# mcu_side.net
KiCad netlist of a schematic drawn in EAGLE
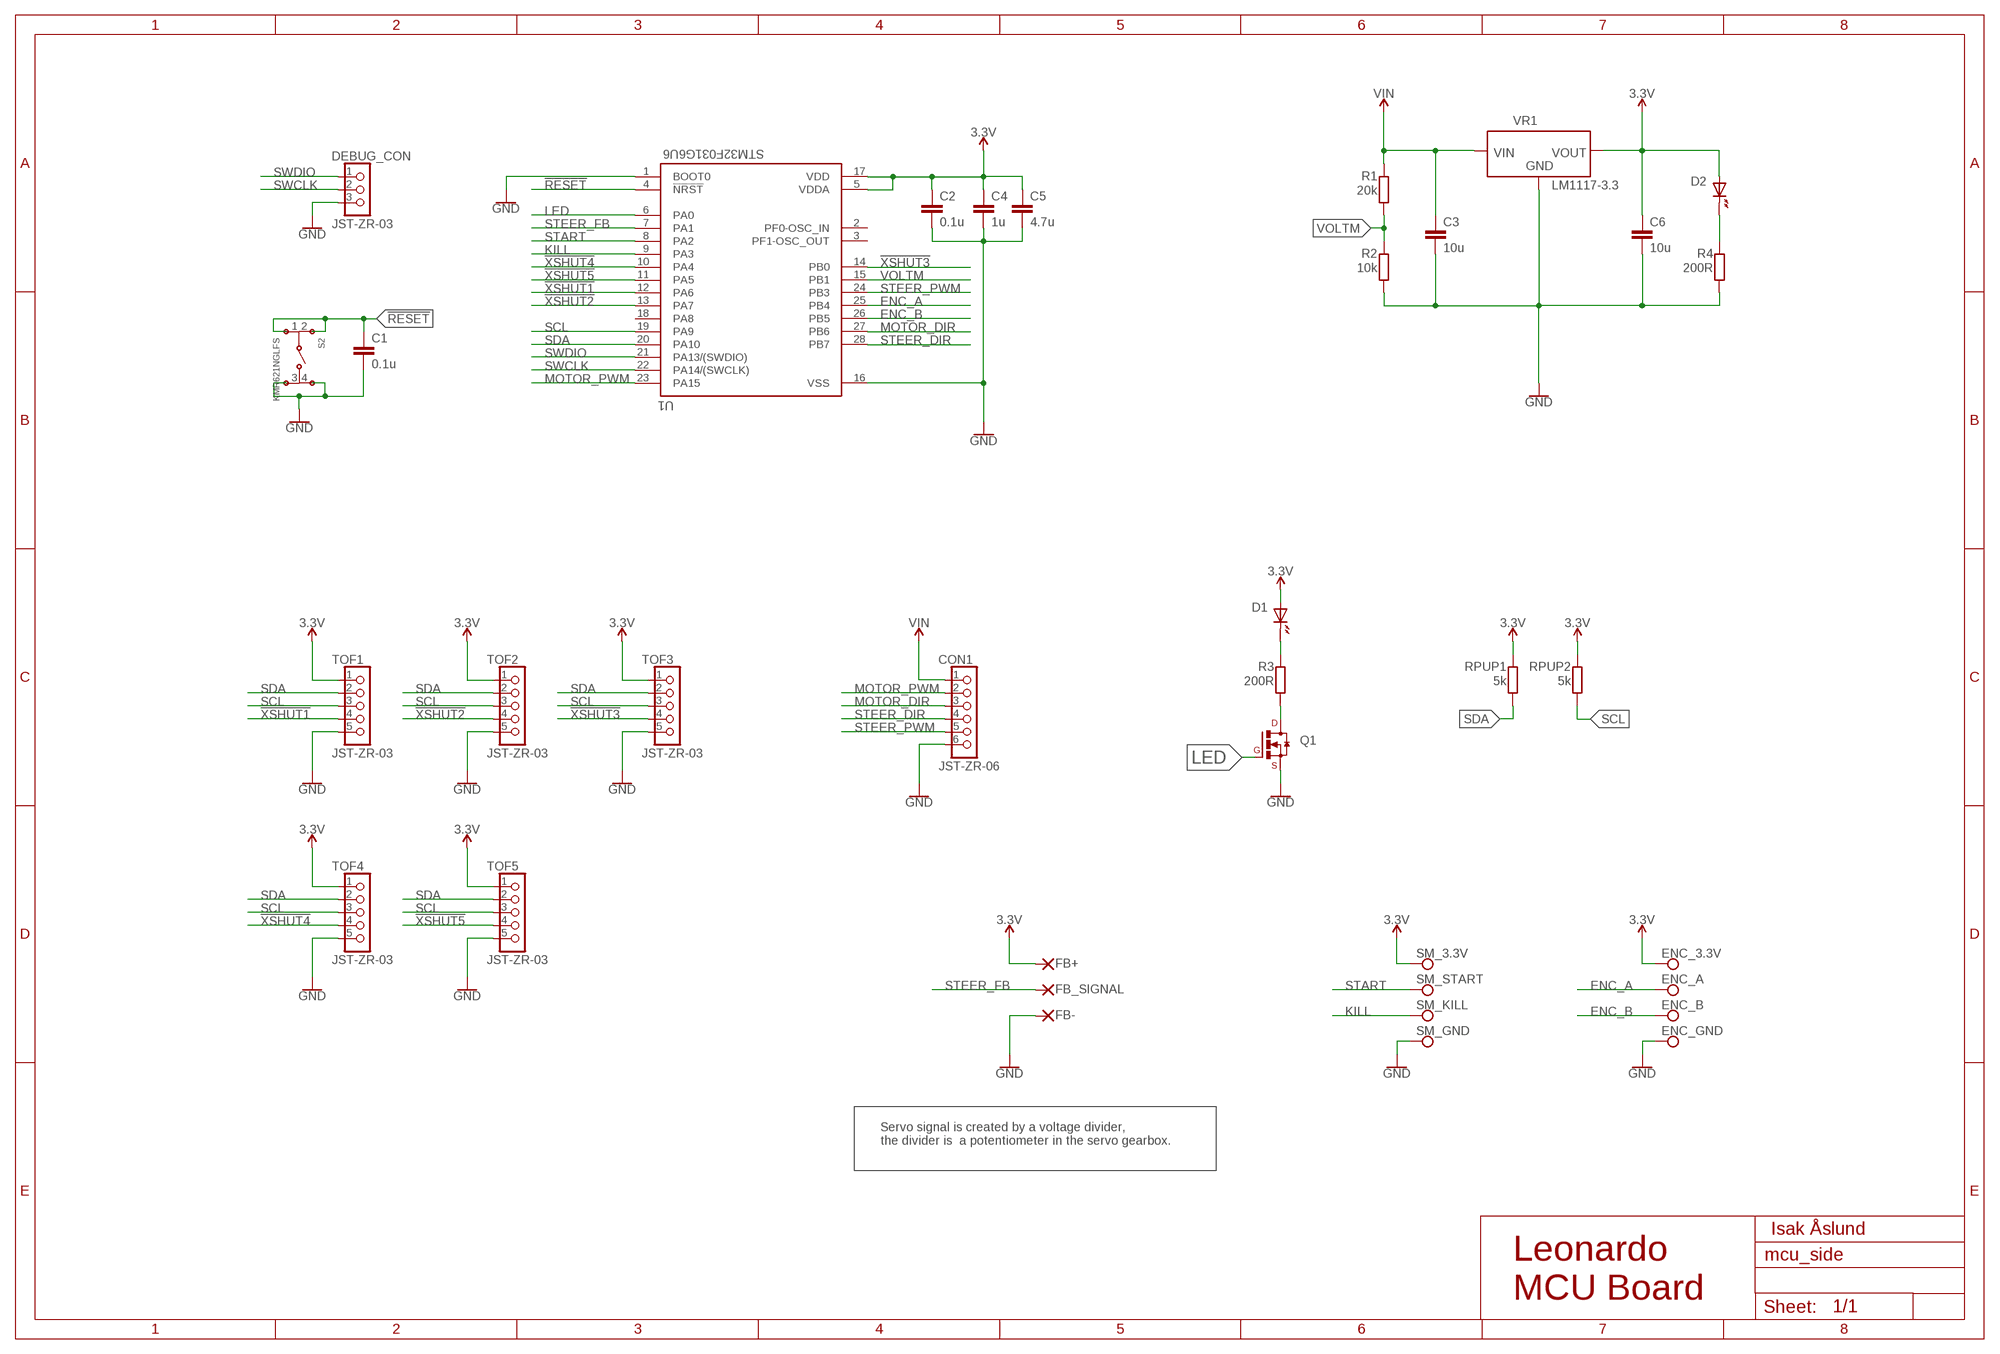
[diagram p0: schematic, sheet 1]

(export (version "E")
  (design (tool "Eeschema 10.0.6"))
  (components
    (comp (ref "C1")
      (value "0.1u")
      (footprint "eagle-import:C0603")
      (libsource (lib "eagle-import") (part "C0603"))
    )
    (comp (ref "C2")
      (value "0.1u")
      (footprint "eagle-import:C0603")
      (libsource (lib "eagle-import") (part "C0603"))
    )
    (comp (ref "C3")
      (value "10u")
      (footprint "eagle-import:C1206")
      (libsource (lib "eagle-import") (part "C1206"))
    )
    (comp (ref "C4")
      (value "1u")
      (footprint "eagle-import:C0603")
      (libsource (lib "eagle-import") (part "C0603"))
    )
    (comp (ref "C5")
      (value "4.7u")
      (footprint "eagle-import:C0603")
      (libsource (lib "eagle-import") (part "C0603"))
    )
    (comp (ref "C6")
      (value "10u")
      (footprint "eagle-import:C1206")
      (libsource (lib "eagle-import") (part "C1206"))
    )
    (comp (ref "CON1")
      (value "JST-ZR-06")
      (footprint "eagle-import:B6B-ZR")
      (libsource (lib "eagle-import") (part "ZR_B6B-ZR"))
    )
    (comp (ref "D1")
      (value "CHIP-LED0603")
      (footprint "eagle-import:CHIP-LED0603")
      (libsource (lib "eagle-import") (part "CHIP-LED0603"))
    )
    (comp (ref "D2")
      (value "CHIP-LED0603")
      (footprint "eagle-import:CHIP-LED0603")
      (libsource (lib "eagle-import") (part "CHIP-LED0603"))
    )
    (comp (ref "DEBUG_CON")
      (value "JST-ZR-03")
      (footprint "eagle-import:B3B-ZR")
      (libsource (lib "eagle-import") (part "ZR_B3B-ZR"))
    )
    (comp (ref "ENC_3.3V")
      (value "PAD-SMD-ROUND-1.27PAD")
      (footprint "eagle-import:PAD.03X.05")
      (libsource (lib "eagle-import") (part "PAD-SMD-ROUND-1.27PAD"))
    )
    (comp (ref "ENC_A")
      (value "PAD-SMD-ROUND-1.27PAD")
      (footprint "eagle-import:PAD.03X.05")
      (libsource (lib "eagle-import") (part "PAD-SMD-ROUND-1.27PAD"))
    )
    (comp (ref "ENC_B")
      (value "PAD-SMD-ROUND-1.27PAD")
      (footprint "eagle-import:PAD.03X.05")
      (libsource (lib "eagle-import") (part "PAD-SMD-ROUND-1.27PAD"))
    )
    (comp (ref "ENC_GND")
      (value "PAD-SMD-ROUND-1.27PAD")
      (footprint "eagle-import:PAD.03X.05")
      (libsource (lib "eagle-import") (part "PAD-SMD-ROUND-1.27PAD"))
    )
    (comp (ref "FB+")
      (value "SMD2")
      (footprint "eagle-import:SMD1,27-2,54")
      (libsource (lib "eagle-import") (part "SMD2"))
    )
    (comp (ref "FB-")
      (value "SMD2")
      (footprint "eagle-import:SMD1,27-2,54")
      (libsource (lib "eagle-import") (part "SMD2"))
    )
    (comp (ref "FB_SIGNAL")
      (value "SMD2")
      (footprint "eagle-import:SMD1,27-2,54")
      (libsource (lib "eagle-import") (part "SMD2"))
    )
    (comp (ref "Q1")
      (value "BSS138LT3G")
      (footprint "eagle-import:SOT23")
      (libsource (lib "eagle-import") (part "BSS138LT3G"))
    )
    (comp (ref "R1")
      (value "20k")
      (footprint "eagle-import:R0603")
      (libsource (lib "eagle-import") (part "R0603"))
    )
    (comp (ref "R2")
      (value "10k")
      (footprint "eagle-import:R0603")
      (libsource (lib "eagle-import") (part "R0603"))
    )
    (comp (ref "R3")
      (value "200R")
      (footprint "eagle-import:R0603")
      (libsource (lib "eagle-import") (part "R0603"))
    )
    (comp (ref "R4")
      (value "200R")
      (footprint "eagle-import:R0603")
      (libsource (lib "eagle-import") (part "R0603"))
    )
    (comp (ref "RPUP1")
      (value "5k")
      (footprint "eagle-import:R0603")
      (libsource (lib "eagle-import") (part "R0603"))
    )
    (comp (ref "RPUP2")
      (value "5k")
      (footprint "eagle-import:R0603")
      (libsource (lib "eagle-import") (part "R0603"))
    )
    (comp (ref "S2")
      (value "KMR621NGLFS")
      (footprint "eagle-import:KMR621NGLFS")
      (libsource (lib "eagle-import") (part "KMR621NGLFS"))
    )
    (comp (ref "SM_3.3V")
      (value "PAD-SMD-ROUND-1.27PAD")
      (footprint "eagle-import:PAD.03X.05")
      (libsource (lib "eagle-import") (part "PAD-SMD-ROUND-1.27PAD"))
    )
    (comp (ref "SM_GND")
      (value "PAD-SMD-ROUND-1.27PAD")
      (footprint "eagle-import:PAD.03X.05")
      (libsource (lib "eagle-import") (part "PAD-SMD-ROUND-1.27PAD"))
    )
    (comp (ref "SM_KILL")
      (value "PAD-SMD-ROUND-1.27PAD")
      (footprint "eagle-import:PAD.03X.05")
      (libsource (lib "eagle-import") (part "PAD-SMD-ROUND-1.27PAD"))
    )
    (comp (ref "SM_START")
      (value "PAD-SMD-ROUND-1.27PAD")
      (footprint "eagle-import:PAD.03X.05")
      (libsource (lib "eagle-import") (part "PAD-SMD-ROUND-1.27PAD"))
    )
    (comp (ref "TOF1")
      (value "JST-ZR-03")
      (footprint "eagle-import:B5B-ZR")
      (libsource (lib "eagle-import") (part "ZR_B5B-ZR"))
    )
    (comp (ref "TOF2")
      (value "JST-ZR-03")
      (footprint "eagle-import:B5B-ZR")
      (libsource (lib "eagle-import") (part "ZR_B5B-ZR"))
    )
    (comp (ref "TOF3")
      (value "JST-ZR-03")
      (footprint "eagle-import:B5B-ZR")
      (libsource (lib "eagle-import") (part "ZR_B5B-ZR"))
    )
    (comp (ref "TOF4")
      (value "JST-ZR-03")
      (footprint "eagle-import:B5B-ZR")
      (libsource (lib "eagle-import") (part "ZR_B5B-ZR"))
    )
    (comp (ref "TOF5")
      (value "JST-ZR-03")
      (footprint "eagle-import:B5B-ZR")
      (libsource (lib "eagle-import") (part "ZR_B5B-ZR"))
    )
    (comp (ref "U1")
      (value "STM32F031G6U6")
      (footprint "eagle-import:QFN50P400X400X60-28N")
      (fields (field (name "MF") "STMicroelectronics"))
      (libsource (lib "eagle-import") (part "STM32F031G6U6"))
    )
    (comp (ref "VR1")
      (value "LM1117-3.3")
      (footprint "eagle-import:SOT230P700X180-4")
      (libsource (lib "eagle-import") (part "LM1117-3.3"))
    )
  )
  (nets
    (net (code "1") (name "/ENC_A") (class "Default")
      (node (ref "ENC_A") (pin "P$1") (pinfunction "1_P$1") (pintype "bidirectional"))
      (node (ref "U1") (pin "25") (pinfunction "PB4_25") (pintype "bidirectional"))
    )
    (net (code "2") (name "/ENC_B") (class "Default")
      (node (ref "ENC_B") (pin "P$1") (pinfunction "1_P$1") (pintype "bidirectional"))
      (node (ref "U1") (pin "26") (pinfunction "PB5_26") (pintype "bidirectional"))
    )
    (net (code "3") (name "/KILL") (class "Default")
      (node (ref "SM_KILL") (pin "P$1") (pinfunction "1_P$1") (pintype "bidirectional"))
      (node (ref "U1") (pin "9") (pinfunction "PA3_9") (pintype "bidirectional"))
    )
    (net (code "4") (name "/MOTOR_DIR") (class "Default")
      (node (ref "CON1") (pin "3") (pinfunction "3_3") (pintype "passive"))
      (node (ref "U1") (pin "27") (pinfunction "PB6_27") (pintype "bidirectional"))
    )
    (net (code "5") (name "/MOTOR_PWM") (class "Default")
      (node (ref "CON1") (pin "2") (pinfunction "2_2") (pintype "passive"))
      (node (ref "U1") (pin "23") (pinfunction "PA15_23") (pintype "bidirectional"))
    )
    (net (code "6") (name "/START") (class "Default")
      (node (ref "SM_START") (pin "P$1") (pinfunction "1_P$1") (pintype "bidirectional"))
      (node (ref "U1") (pin "8") (pinfunction "PA2_8") (pintype "bidirectional"))
    )
    (net (code "7") (name "/STEER_DIR") (class "Default")
      (node (ref "CON1") (pin "4") (pinfunction "4_4") (pintype "passive"))
      (node (ref "U1") (pin "28") (pinfunction "PB7_28") (pintype "bidirectional"))
    )
    (net (code "8") (name "/STEER_FB") (class "Default")
      (node (ref "FB_SIGNAL") (pin "1") (pinfunction "P_1") (pintype "passive"))
      (node (ref "U1") (pin "7") (pinfunction "PA1_7") (pintype "bidirectional"))
    )
    (net (code "9") (name "/STEER_PWM") (class "Default")
      (node (ref "CON1") (pin "5") (pinfunction "5_5") (pintype "passive"))
      (node (ref "U1") (pin "24") (pinfunction "PB3_24") (pintype "bidirectional"))
    )
    (net (code "10") (name "/SWCLK") (class "Default")
      (node (ref "DEBUG_CON") (pin "2") (pinfunction "2_2") (pintype "passive"))
      (node (ref "U1") (pin "22") (pinfunction "PA14/(SWCLK)_22") (pintype "bidirectional"))
    )
    (net (code "11") (name "/SWDIO") (class "Default")
      (node (ref "DEBUG_CON") (pin "1") (pinfunction "1_1") (pintype "passive"))
      (node (ref "U1") (pin "21") (pinfunction "PA13/(SWDIO)_21") (pintype "bidirectional"))
    )
    (net (code "12") (name "/~{RESET}") (class "Default")
      (node (ref "C1") (pin "1") (pinfunction "1_1") (pintype "passive"))
      (node (ref "S2") (pin "1") (pinfunction "1_1") (pintype "bidirectional"))
      (node (ref "S2") (pin "2") (pinfunction "2_2") (pintype "bidirectional"))
      (node (ref "U1") (pin "4") (pinfunction "~{NRST}_4") (pintype "bidirectional"))
    )
    (net (code "13") (name "/~{XSHUT1}") (class "Default")
      (node (ref "TOF1") (pin "4") (pinfunction "4_4") (pintype "passive"))
      (node (ref "U1") (pin "12") (pinfunction "PA6_12") (pintype "bidirectional"))
    )
    (net (code "14") (name "/~{XSHUT2}") (class "Default")
      (node (ref "TOF2") (pin "4") (pinfunction "4_4") (pintype "passive"))
      (node (ref "U1") (pin "13") (pinfunction "PA7_13") (pintype "bidirectional"))
    )
    (net (code "15") (name "/~{XSHUT3}") (class "Default")
      (node (ref "TOF3") (pin "4") (pinfunction "4_4") (pintype "passive"))
      (node (ref "U1") (pin "14") (pinfunction "PB0_14") (pintype "bidirectional"))
    )
    (net (code "16") (name "/~{XSHUT4}") (class "Default")
      (node (ref "TOF4") (pin "4") (pinfunction "4_4") (pintype "passive"))
      (node (ref "U1") (pin "10") (pinfunction "PA4_10") (pintype "bidirectional"))
    )
    (net (code "17") (name "/~{XSHUT5}") (class "Default")
      (node (ref "TOF5") (pin "4") (pinfunction "4_4") (pintype "passive"))
      (node (ref "U1") (pin "11") (pinfunction "PA5_11") (pintype "bidirectional"))
    )
    (net (code "18") (name "3.3V") (class "Default")
      (node (ref "C2") (pin "1") (pinfunction "1_1") (pintype "passive"))
      (node (ref "C4") (pin "1") (pinfunction "1_1") (pintype "passive"))
      (node (ref "C5") (pin "1") (pinfunction "1_1") (pintype "passive"))
      (node (ref "C6") (pin "1") (pinfunction "1_1") (pintype "passive"))
      (node (ref "D1") (pin "A") (pinfunction "A_A") (pintype "passive"))
      (node (ref "D2") (pin "A") (pinfunction "A_A") (pintype "passive"))
      (node (ref "ENC_3.3V") (pin "P$1") (pinfunction "1_P$1") (pintype "bidirectional"))
      (node (ref "FB+") (pin "1") (pinfunction "P_1") (pintype "passive"))
      (node (ref "RPUP1") (pin "1") (pinfunction "1_1") (pintype "passive"))
      (node (ref "RPUP2") (pin "1") (pinfunction "1_1") (pintype "passive"))
      (node (ref "SM_3.3V") (pin "P$1") (pinfunction "1_P$1") (pintype "bidirectional"))
      (node (ref "TOF1") (pin "1") (pinfunction "1_1") (pintype "passive"))
      (node (ref "TOF2") (pin "1") (pinfunction "1_1") (pintype "passive"))
      (node (ref "TOF3") (pin "1") (pinfunction "1_1") (pintype "passive"))
      (node (ref "TOF4") (pin "1") (pinfunction "1_1") (pintype "passive"))
      (node (ref "TOF5") (pin "1") (pinfunction "1_1") (pintype "passive"))
      (node (ref "U1") (pin "17") (pinfunction "VDD_17") (pintype "power_in"))
      (node (ref "U1") (pin "5") (pinfunction "VDDA_5") (pintype "power_in"))
      (node (ref "VR1") (pin "2") (pinfunction "VOUT_2") (pintype "power_in"))
      (node (ref "VR1") (pin "4") (pinfunction "VOUT_4") (pintype "power_in"))
    )
    (net (code "19") (name "GND") (class "Default")
      (node (ref "C1") (pin "2") (pinfunction "2_2") (pintype "passive"))
      (node (ref "C2") (pin "2") (pinfunction "2_2") (pintype "passive"))
      (node (ref "C3") (pin "2") (pinfunction "2_2") (pintype "passive"))
      (node (ref "C4") (pin "2") (pinfunction "2_2") (pintype "passive"))
      (node (ref "C5") (pin "2") (pinfunction "2_2") (pintype "passive"))
      (node (ref "C6") (pin "2") (pinfunction "2_2") (pintype "passive"))
      (node (ref "CON1") (pin "6") (pinfunction "6_6") (pintype "passive"))
      (node (ref "DEBUG_CON") (pin "3") (pinfunction "3_3") (pintype "passive"))
      (node (ref "ENC_GND") (pin "P$1") (pinfunction "1_P$1") (pintype "bidirectional"))
      (node (ref "FB-") (pin "1") (pinfunction "P_1") (pintype "passive"))
      (node (ref "Q1") (pin "2") (pinfunction "S_2") (pintype "passive"))
      (node (ref "R2") (pin "2") (pinfunction "2_2") (pintype "passive"))
      (node (ref "R4") (pin "2") (pinfunction "2_2") (pintype "passive"))
      (node (ref "S2") (pin "3") (pinfunction "3_3") (pintype "bidirectional"))
      (node (ref "S2") (pin "4") (pinfunction "4_4") (pintype "bidirectional"))
      (node (ref "SM_GND") (pin "P$1") (pinfunction "1_P$1") (pintype "bidirectional"))
      (node (ref "TOF1") (pin "5") (pinfunction "5_5") (pintype "passive"))
      (node (ref "TOF2") (pin "5") (pinfunction "5_5") (pintype "passive"))
      (node (ref "TOF3") (pin "5") (pinfunction "5_5") (pintype "passive"))
      (node (ref "TOF4") (pin "5") (pinfunction "5_5") (pintype "passive"))
      (node (ref "TOF5") (pin "5") (pinfunction "5_5") (pintype "passive"))
      (node (ref "U1") (pin "1") (pinfunction "BOOT0_1") (pintype "input"))
      (node (ref "U1") (pin "16") (pinfunction "VSS_16") (pintype "power_in"))
      (node (ref "VR1") (pin "1") (pinfunction "GND_1") (pintype "power_in"))
    )
    (net (code "20") (name "LED") (class "Default")
      (node (ref "Q1") (pin "1") (pinfunction "G_1") (pintype "passive"))
      (node (ref "U1") (pin "6") (pinfunction "PA0_6") (pintype "bidirectional"))
    )
    (net (code "21") (name "Net-(D1-K)") (class "Default")
      (node (ref "D1") (pin "C") (pinfunction "K_C") (pintype "passive"))
      (node (ref "R3") (pin "1") (pinfunction "1_1") (pintype "passive"))
    )
    (net (code "22") (name "Net-(D2-K)") (class "Default")
      (node (ref "D2") (pin "C") (pinfunction "K_C") (pintype "passive"))
      (node (ref "R4") (pin "1") (pinfunction "1_1") (pintype "passive"))
    )
    (net (code "23") (name "Net-(Q1-D)") (class "Default")
      (node (ref "Q1") (pin "3") (pinfunction "D_3") (pintype "passive"))
      (node (ref "R3") (pin "2") (pinfunction "2_2") (pintype "passive"))
    )
    (net (code "24") (name "SCL") (class "Default")
      (node (ref "RPUP2") (pin "2") (pinfunction "2_2") (pintype "passive"))
      (node (ref "TOF1") (pin "3") (pinfunction "3_3") (pintype "passive"))
      (node (ref "TOF2") (pin "3") (pinfunction "3_3") (pintype "passive"))
      (node (ref "TOF3") (pin "3") (pinfunction "3_3") (pintype "passive"))
      (node (ref "TOF4") (pin "3") (pinfunction "3_3") (pintype "passive"))
      (node (ref "TOF5") (pin "3") (pinfunction "3_3") (pintype "passive"))
      (node (ref "U1") (pin "19") (pinfunction "PA9_19") (pintype "bidirectional"))
    )
    (net (code "25") (name "SDA") (class "Default")
      (node (ref "RPUP1") (pin "2") (pinfunction "2_2") (pintype "passive"))
      (node (ref "TOF1") (pin "2") (pinfunction "2_2") (pintype "passive"))
      (node (ref "TOF2") (pin "2") (pinfunction "2_2") (pintype "passive"))
      (node (ref "TOF3") (pin "2") (pinfunction "2_2") (pintype "passive"))
      (node (ref "TOF4") (pin "2") (pinfunction "2_2") (pintype "passive"))
      (node (ref "TOF5") (pin "2") (pinfunction "2_2") (pintype "passive"))
      (node (ref "U1") (pin "20") (pinfunction "PA10_20") (pintype "bidirectional"))
    )
    (net (code "26") (name "VIN") (class "Default")
      (node (ref "C3") (pin "1") (pinfunction "1_1") (pintype "passive"))
      (node (ref "CON1") (pin "1") (pinfunction "1_1") (pintype "passive"))
      (node (ref "R1") (pin "1") (pinfunction "1_1") (pintype "passive"))
      (node (ref "VR1") (pin "3") (pinfunction "VIN_3") (pintype "power_in"))
    )
    (net (code "27") (name "VOLTM") (class "Default")
      (node (ref "R1") (pin "2") (pinfunction "2_2") (pintype "passive"))
      (node (ref "R2") (pin "1") (pinfunction "1_1") (pintype "passive"))
      (node (ref "U1") (pin "15") (pinfunction "PB1_15") (pintype "bidirectional"))
    )
    (net (code "28") (name "unconnected-(U1-PA8-Pad18)") (class "Default")
      (node (ref "U1") (pin "18") (pinfunction "PA8_18") (pintype "bidirectional"))
    )
    (net (code "29") (name "unconnected-(U1-PF0-OSC_IN-Pad2)") (class "Default")
      (node (ref "U1") (pin "2") (pinfunction "PF0-OSC_IN_2") (pintype "bidirectional"))
    )
    (net (code "30") (name "unconnected-(U1-PF1-OSC_OUT-Pad3)") (class "Default")
      (node (ref "U1") (pin "3") (pinfunction "PF1-OSC_OUT_3") (pintype "bidirectional"))
    )
  )
)
